# OpenReader_Schematic.net
KiCad netlist of a schematic drawn in EAGLE
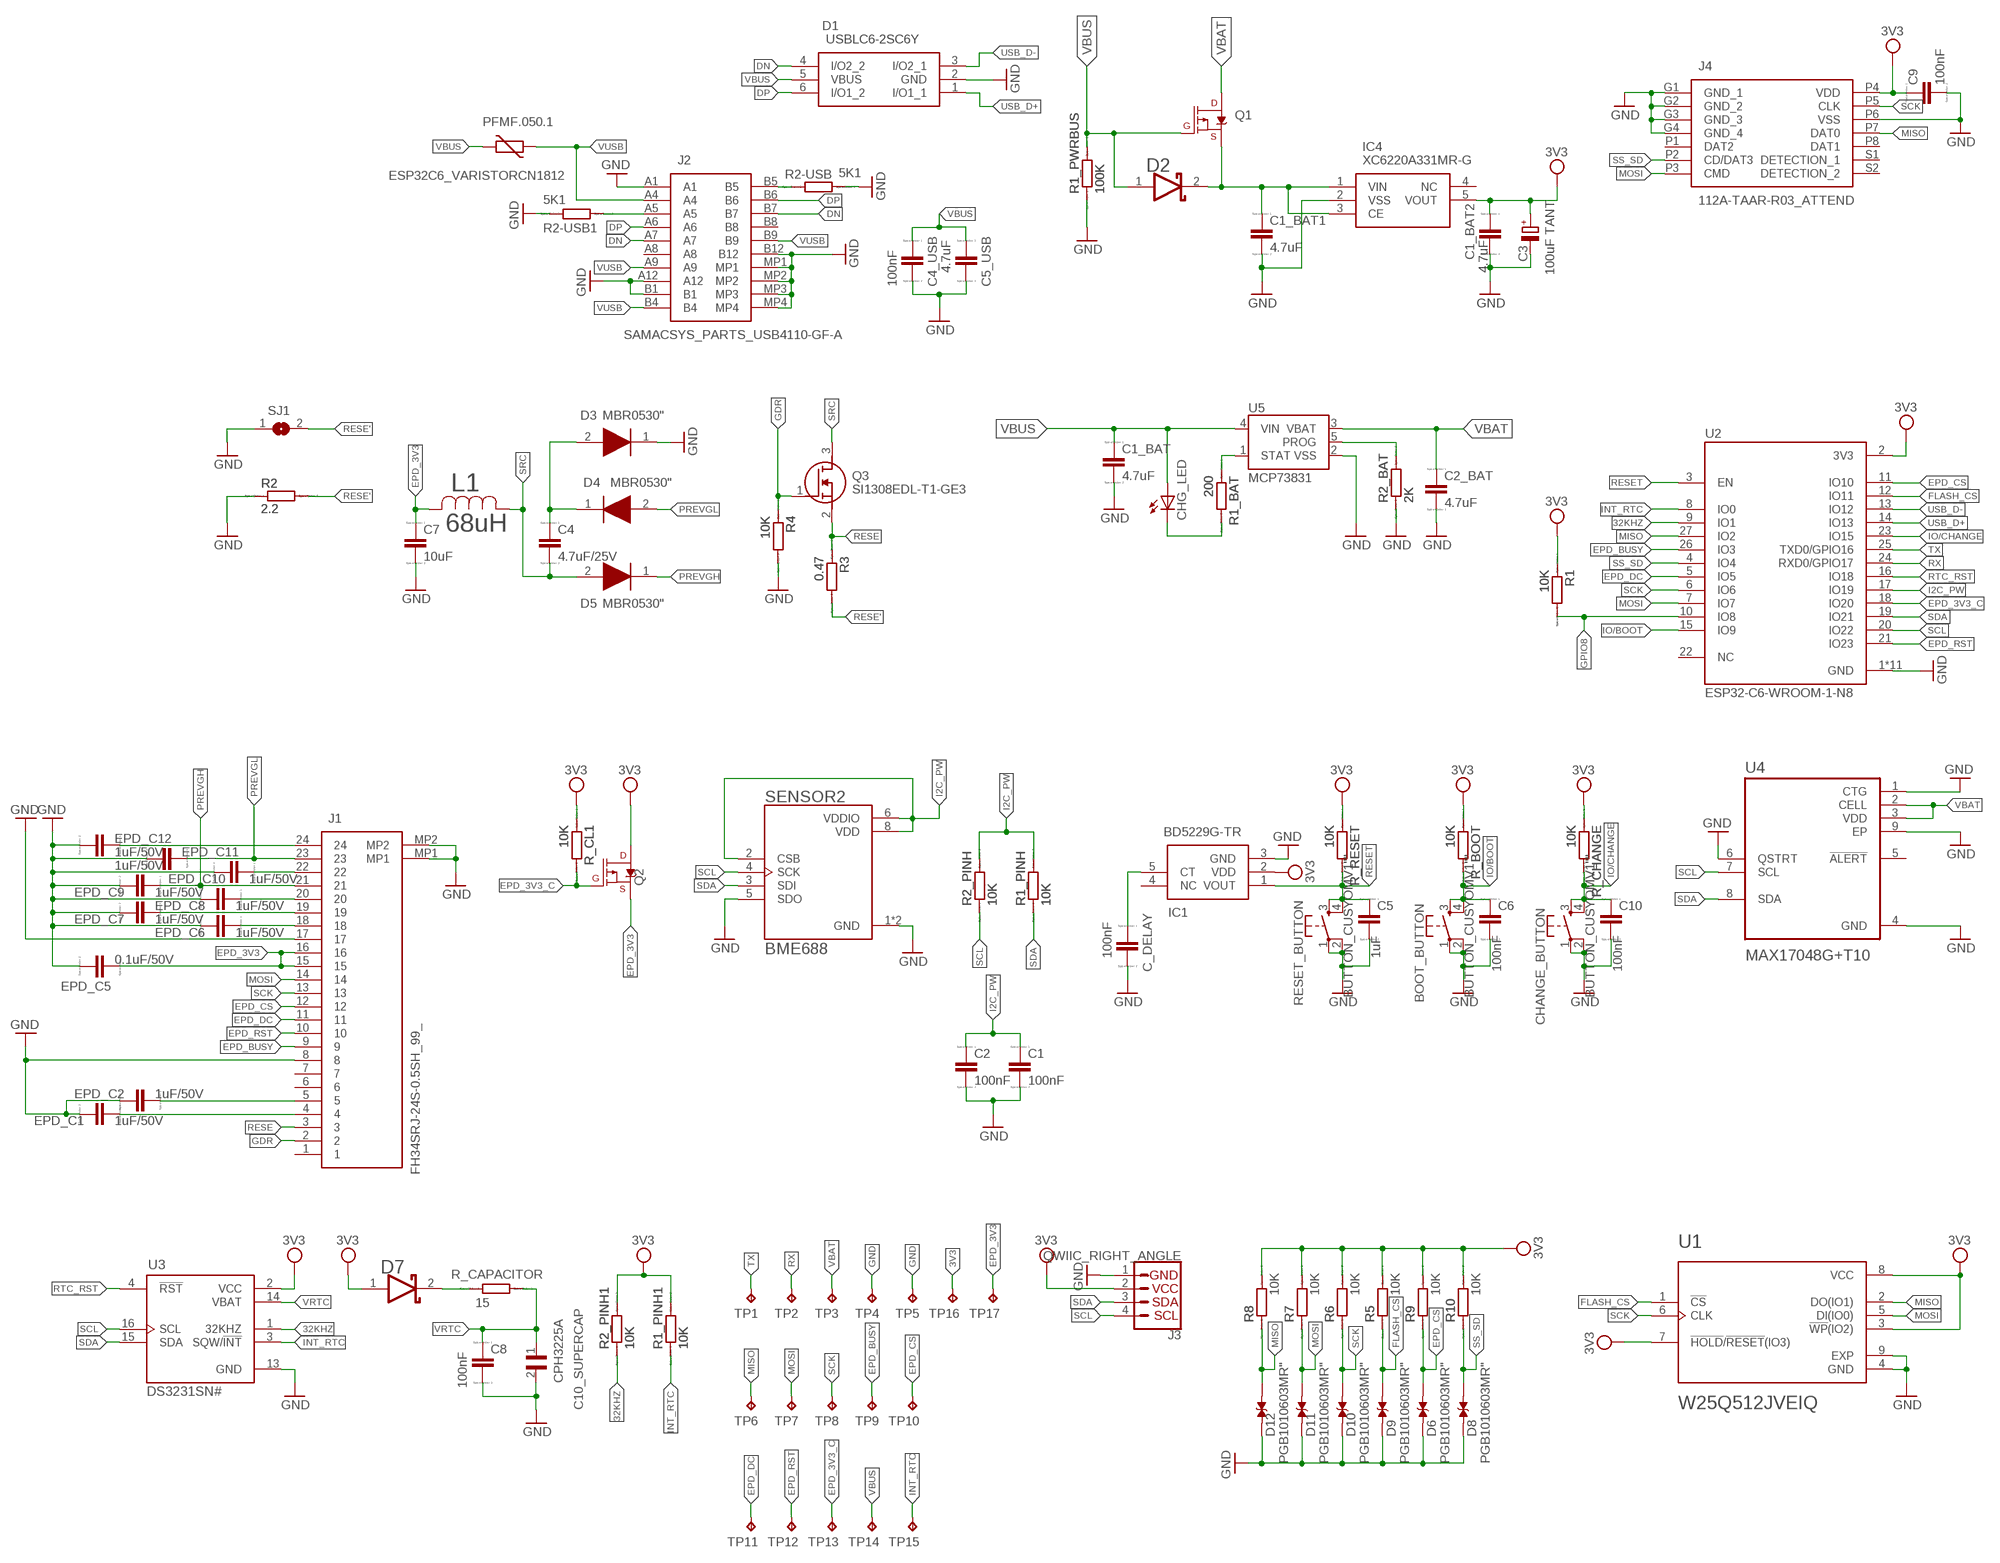
[diagram p0: schematic, sheet 1]

(export (version "E")
  (design (tool "Eeschema 10.0.6"))
  (components
    (comp (ref "BOOT_BUTTON")
      (value "BUTTON_CUSYOMV1\"\"")
      (footprint "eagle-import:MYBUTTON")
      (libsource (lib "eagle-import") (part "BUTTON_CUSYOMV1{dblquote}"))
    )
    (comp (ref "C1")
      (value "100nF")
      (footprint "eagle-import:EAGLE-LTSPICE_C0402")
      (libsource (lib "eagle-import") (part "EAGLE-LTSPICE_CC0402"))
    )
    (comp (ref "C1_BAT")
      (value "4.7uF")
      (footprint "eagle-import:EAGLE-LTSPICE_C0402")
      (libsource (lib "eagle-import") (part "EAGLE-LTSPICE_CC0402"))
    )
    (comp (ref "C1_BAT1")
      (value "4.7uF")
      (footprint "eagle-import:EAGLE-LTSPICE_C0402")
      (libsource (lib "eagle-import") (part "EAGLE-LTSPICE_CC0402"))
    )
    (comp (ref "C1_BAT2")
      (value "4.7uF")
      (footprint "eagle-import:EAGLE-LTSPICE_C0402")
      (libsource (lib "eagle-import") (part "EAGLE-LTSPICE_CC0402"))
    )
    (comp (ref "C2")
      (value "100nF")
      (footprint "eagle-import:EAGLE-LTSPICE_C0402")
      (libsource (lib "eagle-import") (part "EAGLE-LTSPICE_CC0402"))
    )
    (comp (ref "C2_BAT")
      (value "4.7uF")
      (footprint "eagle-import:EAGLE-LTSPICE_C0402")
      (libsource (lib "eagle-import") (part "EAGLE-LTSPICE_CC0402"))
    )
    (comp (ref "C3")
      (value "100uF TANT")
      (footprint "eagle-import:RCL_CT3528")
      (libsource (lib "eagle-import") (part "RCL_CPOL-EUCT3528"))
    )
    (comp (ref "C4")
      (value "4.7uF/25V")
      (footprint "eagle-import:EAGLE-LTSPICE_C0402")
      (libsource (lib "eagle-import") (part "EAGLE-LTSPICE_CC0402"))
    )
    (comp (ref "C4_USB")
      (value "100nF")
      (footprint "eagle-import:EAGLE-LTSPICE_C0402")
      (libsource (lib "eagle-import") (part "EAGLE-LTSPICE_CC0402"))
    )
    (comp (ref "C5")
      (value "1uF")
      (footprint "eagle-import:EAGLE-LTSPICE_C0402")
      (libsource (lib "eagle-import") (part "EAGLE-LTSPICE_CC0402"))
    )
    (comp (ref "C5_USB")
      (value "4.7uF")
      (footprint "eagle-import:EAGLE-LTSPICE_C0402")
      (libsource (lib "eagle-import") (part "EAGLE-LTSPICE_CC0402"))
    )
    (comp (ref "C6")
      (value "100nF")
      (footprint "eagle-import:EAGLE-LTSPICE_C0402")
      (libsource (lib "eagle-import") (part "EAGLE-LTSPICE_CC0402"))
    )
    (comp (ref "C7")
      (value "10uF")
      (footprint "eagle-import:EAGLE-LTSPICE_C0402")
      (libsource (lib "eagle-import") (part "EAGLE-LTSPICE_CC0402"))
    )
    (comp (ref "C8")
      (value "100nF")
      (footprint "eagle-import:EAGLE-LTSPICE_C0402")
      (libsource (lib "eagle-import") (part "EAGLE-LTSPICE_CC0402"))
    )
    (comp (ref "C9")
      (value "100nF")
      (footprint "eagle-import:EAGLE-LTSPICE_C0402")
      (libsource (lib "eagle-import") (part "EAGLE-LTSPICE_CC0402"))
    )
    (comp (ref "C10")
      (value "100nF")
      (footprint "eagle-import:EAGLE-LTSPICE_C0402")
      (libsource (lib "eagle-import") (part "EAGLE-LTSPICE_CC0402"))
    )
    (comp (ref "C10_SUPERCAP")
      (value "CPH3225A")
      (footprint "eagle-import:CAPCP3225X100N")
      (fields (field (name "MF") "Seiko Instruments"))
      (libsource (lib "eagle-import") (part "CPH3225A"))
    )
    (comp (ref "CHANGE_BUTTON")
      (value "BUTTON_CUSYOMV1\"\"")
      (footprint "eagle-import:MYBUTTON")
      (libsource (lib "eagle-import") (part "BUTTON_CUSYOMV1{dblquote}"))
    )
    (comp (ref "CHG_LED")
      (value "ADAFRUIT_LEDCHIP-LED0603")
      (footprint "eagle-import:ADAFRUIT_CHIP-LED0603")
      (libsource (lib "eagle-import") (part "ADAFRUIT_LEDCHIP-LED0603"))
    )
    (comp (ref "C_DELAY")
      (value "100nF")
      (footprint "eagle-import:EAGLE-LTSPICE_C0402")
      (libsource (lib "eagle-import") (part "EAGLE-LTSPICE_CC0402"))
    )
    (comp (ref "D1")
      (value "USBLC6-2SC6Y")
      (footprint "eagle-import:SOT95P280X145-6N")
      (fields (field (name "MF") "STMicroelectronics"))
      (libsource (lib "eagle-import") (part "USBLC6-2SC6Y"))
    )
    (comp (ref "D2")
      (value "ESP32_WROVER_AVX---SD0805S020S1R0_AVX_SD0805S020S1R0_0_0AVX_SD0805S020S1R0_0_0")
      (footprint "eagle-import:ESP32_WROVER_AVX---SD0805S020S1R0_AVX_SD0805S020S1R0_0")
      (libsource (lib "eagle-import") (part "ESP32_WROVER_AVX---SD0805S020S1R0_AVX_SD0805S020S1R0_0_0AVX_SD0805S020S1R0_0_0"))
    )
    (comp (ref "D3")
      (value "MBR0530\"")
      (footprint "eagle-import:SOD3716X135N")
      (libsource (lib "eagle-import") (part "MBR0530{dblquote}"))
    )
    (comp (ref "D4")
      (value "MBR0530\"")
      (footprint "eagle-import:SOD3716X135N")
      (libsource (lib "eagle-import") (part "MBR0530{dblquote}"))
    )
    (comp (ref "D5")
      (value "MBR0530\"")
      (footprint "eagle-import:SOD3716X135N")
      (libsource (lib "eagle-import") (part "MBR0530{dblquote}"))
    )
    (comp (ref "D6")
      (value "PGB1010603MR\"")
      (footprint "eagle-import:DIOC1608X36N")
      (libsource (lib "eagle-import") (part "PGB1010603MR{dblquote}"))
    )
    (comp (ref "D7")
      (value "ESP32_WROVER_AVX---SD0805S020S1R0_AVX_SD0805S020S1R0_0_0AVX_SD0805S020S1R0_0_0")
      (footprint "eagle-import:ESP32_WROVER_AVX---SD0805S020S1R0_AVX_SD0805S020S1R0_0")
      (libsource (lib "eagle-import") (part "ESP32_WROVER_AVX---SD0805S020S1R0_AVX_SD0805S020S1R0_0_0AVX_SD0805S020S1R0_0_0"))
    )
    (comp (ref "D8")
      (value "PGB1010603MR\"")
      (footprint "eagle-import:DIOC1608X36N")
      (libsource (lib "eagle-import") (part "PGB1010603MR{dblquote}"))
    )
    (comp (ref "D9")
      (value "PGB1010603MR\"")
      (footprint "eagle-import:DIOC1608X36N")
      (libsource (lib "eagle-import") (part "PGB1010603MR{dblquote}"))
    )
    (comp (ref "D10")
      (value "PGB1010603MR\"")
      (footprint "eagle-import:DIOC1608X36N")
      (libsource (lib "eagle-import") (part "PGB1010603MR{dblquote}"))
    )
    (comp (ref "D11")
      (value "PGB1010603MR\"")
      (footprint "eagle-import:DIOC1608X36N")
      (libsource (lib "eagle-import") (part "PGB1010603MR{dblquote}"))
    )
    (comp (ref "D12")
      (value "PGB1010603MR\"")
      (footprint "eagle-import:DIOC1608X36N")
      (libsource (lib "eagle-import") (part "PGB1010603MR{dblquote}"))
    )
    (comp (ref "EPD_C1")
      (value "1uF/50V")
      (footprint "eagle-import:EAGLE-LTSPICE_C0402")
      (libsource (lib "eagle-import") (part "EAGLE-LTSPICE_CC0402"))
    )
    (comp (ref "EPD_C2")
      (value "1uF/50V")
      (footprint "eagle-import:EAGLE-LTSPICE_C0402")
      (libsource (lib "eagle-import") (part "EAGLE-LTSPICE_CC0402"))
    )
    (comp (ref "EPD_C5")
      (value "0.1uF/50V")
      (footprint "eagle-import:EAGLE-LTSPICE_C0402")
      (libsource (lib "eagle-import") (part "EAGLE-LTSPICE_CC0402"))
    )
    (comp (ref "EPD_C6")
      (value "1uF/50V")
      (footprint "eagle-import:EAGLE-LTSPICE_C0402")
      (libsource (lib "eagle-import") (part "EAGLE-LTSPICE_CC0402"))
    )
    (comp (ref "EPD_C7")
      (value "1uF/50V")
      (footprint "eagle-import:EAGLE-LTSPICE_C0402")
      (libsource (lib "eagle-import") (part "EAGLE-LTSPICE_CC0402"))
    )
    (comp (ref "EPD_C8")
      (value "1uF/50V")
      (footprint "eagle-import:EAGLE-LTSPICE_C0402")
      (libsource (lib "eagle-import") (part "EAGLE-LTSPICE_CC0402"))
    )
    (comp (ref "EPD_C9")
      (value "1uF/50V")
      (footprint "eagle-import:EAGLE-LTSPICE_C0402")
      (libsource (lib "eagle-import") (part "EAGLE-LTSPICE_CC0402"))
    )
    (comp (ref "EPD_C10")
      (value "1uF/50V")
      (footprint "eagle-import:EAGLE-LTSPICE_C0402")
      (libsource (lib "eagle-import") (part "EAGLE-LTSPICE_CC0402"))
    )
    (comp (ref "EPD_C11")
      (value "1uF/50V")
      (footprint "eagle-import:EAGLE-LTSPICE_C0402")
      (libsource (lib "eagle-import") (part "EAGLE-LTSPICE_CC0402"))
    )
    (comp (ref "EPD_C12")
      (value "1uF/50V")
      (footprint "eagle-import:EAGLE-LTSPICE_C0402")
      (libsource (lib "eagle-import") (part "EAGLE-LTSPICE_CC0402"))
    )
    (comp (ref "IC1")
      (value "BD5229G-TR")
      (footprint "eagle-import:SOT95P280X125-5N")
      (fields (field (name "MOUSER_PART_NUMBER") "755-BD5229G-TR"))
      (libsource (lib "eagle-import") (part "BD5229G-TR"))
    )
    (comp (ref "IC4")
      (value "XC6220A331MR-G")
      (footprint "eagle-import:SOT95P280X120-5N")
      (fields (field (name "MOUSER_PART_NUMBER") "865-XC6220A331MR-G"))
      (libsource (lib "eagle-import") (part "XC6220A331MR-G"))
    )
    (comp (ref "J1")
      (value "FH34SRJ-24S-0.5SH_99_")
      (footprint "eagle-import:FH34SRJ24S05SH99")
      (fields
        (field (name "MANUFACTURER_PART_NUMBER") "FH34SRJ-24S-0.5SH(99)")
        (field (name "MOUSER_PART_NUMBER") "798-FH34SRJ24S05SH99")
      )
      (libsource (lib "eagle-import") (part "FH34SRJ-24S-0.5SH_99_"))
    )
    (comp (ref "J2")
      (value "SAMACSYS_PARTS_USB4110-GF-A")
      (footprint "eagle-import:SAMACSYS_PARTS_USB4110GFA")
      (fields
        (field (name "MANUFACTURER_PART_NUMBER") "USB4110-GF-A")
        (field (name "MOUSER_PART_NUMBER") "640-USB4110-GF-A")
      )
      (libsource (lib "eagle-import") (part "SAMACSYS_PARTS_USB4110-GF-A"))
    )
    (comp (ref "J3")
      (value "QWIIC_RIGHT_ANGLE")
      (footprint "eagle-import:JST04_1MM_RA")
      (libsource (lib "eagle-import") (part "QWIIC_CONNECTORJS-1MM"))
    )
    (comp (ref "J4")
      (value "112A-TAAR-R03_ATTEND")
      (footprint "eagle-import:112ATAARR03ATTEND")
      (fields (field (name "MANUFACTURER_PART_NUMBER") "112A-TAAR-R03 ATTEND"))
      (libsource (lib "eagle-import") (part "112A-TAAR-R03_ATTEND"))
    )
    (comp (ref "L1")
      (value "68uH")
      (footprint "eagle-import:IND_4828-WE-TPC_WRE")
      (fields
        (field (name "MANUFACTURER_PART_NUMBER") "744043680")
        (field (name "COPYRIGHT") "Copyright (C) 2024 Ultra Librarian. All rights reserved.")
      )
      (libsource (lib "eagle-import") (part "744043680IND_4828-WE-TPC_WRE"))
    )
    (comp (ref "PFMF.050.1")
      (value "ESP32C6_VARISTORCN1812")
      (footprint "eagle-import:ESP32C6_VARISTOR_CT_CN1812")
      (libsource (lib "eagle-import") (part "ESP32C6_VARISTORCN1812"))
    )
    (comp (ref "Q1")
      (value "20V/4.2A/52mΩ/1.4W")
      (footprint "eagle-import:ESP32_WROVER_SPARKFUN-DISCRETESEMI_SOT23-3")
      (libsource (lib "eagle-import") (part "ESP32_WROVER_SPARKFUN-DISCRETESEMI_MOSFET_PCH-DMG2305UX-7"))
    )
    (comp (ref "Q2")
      (value "20V/4.2A/52mΩ/1.4W")
      (footprint "eagle-import:ESP32_WROVER_SPARKFUN-DISCRETESEMI_SOT23-3")
      (libsource (lib "eagle-import") (part "ESP32_WROVER_SPARKFUN-DISCRETESEMI_MOSFET_PCH-DMG2305UX-7"))
    )
    (comp (ref "Q3")
      (value "SI1308EDL-T1-GE3")
      (footprint "eagle-import:SOT65P210X110-3N")
      (fields (field (name "MF") "Vishay Siliconix"))
      (libsource (lib "eagle-import") (part "SI1308EDL-T1-GE3"))
    )
    (comp (ref "R1")
      (value "10K")
      (footprint "eagle-import:ESP32_WROVER_EAGLE-LTSPICE_R0402")
      (libsource (lib "eagle-import") (part "ESP32_WROVER_EAGLE-LTSPICE_RR0402"))
    )
    (comp (ref "R1_BAT")
      (value "200")
      (footprint "eagle-import:ESP32_WROVER_EAGLE-LTSPICE_R0402")
      (libsource (lib "eagle-import") (part "ESP32_WROVER_EAGLE-LTSPICE_RR0402"))
    )
    (comp (ref "R1_PINH")
      (value "10K")
      (footprint "eagle-import:ESP32_WROVER_EAGLE-LTSPICE_R0402")
      (libsource (lib "eagle-import") (part "ESP32_WROVER_EAGLE-LTSPICE_RR0402"))
    )
    (comp (ref "R1_PINH1")
      (value "10K")
      (footprint "eagle-import:ESP32_WROVER_EAGLE-LTSPICE_R0402")
      (libsource (lib "eagle-import") (part "ESP32_WROVER_EAGLE-LTSPICE_RR0402"))
    )
    (comp (ref "R1_PWRBUS")
      (value "100K")
      (footprint "eagle-import:ESP32_WROVER_EAGLE-LTSPICE_R0402")
      (libsource (lib "eagle-import") (part "ESP32_WROVER_EAGLE-LTSPICE_RR0402"))
    )
    (comp (ref "R2")
      (value "2.2")
      (footprint "eagle-import:ESP32_WROVER_EAGLE-LTSPICE_R0402")
      (libsource (lib "eagle-import") (part "ESP32_WROVER_EAGLE-LTSPICE_RR0402"))
    )
    (comp (ref "R2-USB")
      (value "5K1")
      (footprint "eagle-import:ESP32_WROVER_EAGLE-LTSPICE_R0402")
      (libsource (lib "eagle-import") (part "ESP32_WROVER_EAGLE-LTSPICE_RR0402"))
    )
    (comp (ref "R2-USB1")
      (value "5K1")
      (footprint "eagle-import:ESP32_WROVER_EAGLE-LTSPICE_R0402")
      (libsource (lib "eagle-import") (part "ESP32_WROVER_EAGLE-LTSPICE_RR0402"))
    )
    (comp (ref "R2_BAT")
      (value "2K")
      (footprint "eagle-import:ESP32_WROVER_EAGLE-LTSPICE_R0402")
      (libsource (lib "eagle-import") (part "ESP32_WROVER_EAGLE-LTSPICE_RR0402"))
    )
    (comp (ref "R2_PINH")
      (value "10K")
      (footprint "eagle-import:ESP32_WROVER_EAGLE-LTSPICE_R0402")
      (libsource (lib "eagle-import") (part "ESP32_WROVER_EAGLE-LTSPICE_RR0402"))
    )
    (comp (ref "R2_PINH1")
      (value "10K")
      (footprint "eagle-import:ESP32_WROVER_EAGLE-LTSPICE_R0402")
      (libsource (lib "eagle-import") (part "ESP32_WROVER_EAGLE-LTSPICE_RR0402"))
    )
    (comp (ref "R3")
      (value "0.47")
      (footprint "eagle-import:ESP32_WROVER_EAGLE-LTSPICE_R0402")
      (libsource (lib "eagle-import") (part "ESP32_WROVER_EAGLE-LTSPICE_RR0402"))
    )
    (comp (ref "R4")
      (value "10K")
      (footprint "eagle-import:ESP32_WROVER_EAGLE-LTSPICE_R0402")
      (libsource (lib "eagle-import") (part "ESP32_WROVER_EAGLE-LTSPICE_RR0402"))
    )
    (comp (ref "R5")
      (value "10K")
      (footprint "eagle-import:ESP32_WROVER_EAGLE-LTSPICE_R0402")
      (libsource (lib "eagle-import") (part "ESP32_WROVER_EAGLE-LTSPICE_RR0402"))
    )
    (comp (ref "R6")
      (value "10K")
      (footprint "eagle-import:ESP32_WROVER_EAGLE-LTSPICE_R0402")
      (libsource (lib "eagle-import") (part "ESP32_WROVER_EAGLE-LTSPICE_RR0402"))
    )
    (comp (ref "R7")
      (value "10K")
      (footprint "eagle-import:ESP32_WROVER_EAGLE-LTSPICE_R0402")
      (libsource (lib "eagle-import") (part "ESP32_WROVER_EAGLE-LTSPICE_RR0402"))
    )
    (comp (ref "R8")
      (value "10K")
      (footprint "eagle-import:ESP32_WROVER_EAGLE-LTSPICE_R0402")
      (libsource (lib "eagle-import") (part "ESP32_WROVER_EAGLE-LTSPICE_RR0402"))
    )
    (comp (ref "R9")
      (value "10K")
      (footprint "eagle-import:ESP32_WROVER_EAGLE-LTSPICE_R0402")
      (libsource (lib "eagle-import") (part "ESP32_WROVER_EAGLE-LTSPICE_RR0402"))
    )
    (comp (ref "R10")
      (value "10K")
      (footprint "eagle-import:ESP32_WROVER_EAGLE-LTSPICE_R0402")
      (libsource (lib "eagle-import") (part "ESP32_WROVER_EAGLE-LTSPICE_RR0402"))
    )
    (comp (ref "RESET_BUTTON")
      (value "BUTTON_CUSYOMV1\"\"")
      (footprint "eagle-import:MYBUTTON")
      (libsource (lib "eagle-import") (part "BUTTON_CUSYOMV1{dblquote}"))
    )
    (comp (ref "R_BOOT")
      (value "10K")
      (footprint "eagle-import:ESP32_WROVER_EAGLE-LTSPICE_R0402")
      (libsource (lib "eagle-import") (part "ESP32_WROVER_EAGLE-LTSPICE_RR0402"))
    )
    (comp (ref "R_CAPACITOR")
      (value "15")
      (footprint "eagle-import:ESP32_WROVER_EAGLE-LTSPICE_R0402")
      (libsource (lib "eagle-import") (part "ESP32_WROVER_EAGLE-LTSPICE_RR0402"))
    )
    (comp (ref "R_CHANGE")
      (value "10K")
      (footprint "eagle-import:ESP32_WROVER_EAGLE-LTSPICE_R0402")
      (libsource (lib "eagle-import") (part "ESP32_WROVER_EAGLE-LTSPICE_RR0402"))
    )
    (comp (ref "R_CL1")
      (value "10K")
      (footprint "eagle-import:ESP32_WROVER_EAGLE-LTSPICE_R0402")
      (libsource (lib "eagle-import") (part "ESP32_WROVER_EAGLE-LTSPICE_RR0402"))
    )
    (comp (ref "R_RESET")
      (value "10K")
      (footprint "eagle-import:ESP32_WROVER_EAGLE-LTSPICE_R0402")
      (libsource (lib "eagle-import") (part "ESP32_WROVER_EAGLE-LTSPICE_RR0402"))
    )
    (comp (ref "SENSOR2")
      (value "BME688")
      (footprint "eagle-import:ESP32_WROVER_BME680_PSON80P300X300X100-8N")
      (fields (field (name "MF") "Bosch Sensortec") (field (name "MP") "BME680"))
      (libsource (lib "eagle-import") (part "ESP32_WROVER_BME680_BME680"))
    )
    (comp (ref "SJ1") (value "SJ") (footprint "eagle-import:SJ") (libsource (lib "eagle-import") (part "SJ")))
    (comp (ref "TP1")
      (value "TPTP20R")
      (footprint "eagle-import:TP20R")
      (libsource (lib "eagle-import") (part "TPTP20R"))
    )
    (comp (ref "TP2")
      (value "TPTP20R")
      (footprint "eagle-import:TP20R")
      (libsource (lib "eagle-import") (part "TPTP20R"))
    )
    (comp (ref "TP3")
      (value "TPTP20R")
      (footprint "eagle-import:TP20R")
      (libsource (lib "eagle-import") (part "TPTP20R"))
    )
    (comp (ref "TP4")
      (value "TPTP20R")
      (footprint "eagle-import:TP20R")
      (libsource (lib "eagle-import") (part "TPTP20R"))
    )
    (comp (ref "TP5")
      (value "TPTP20R")
      (footprint "eagle-import:TP20R")
      (libsource (lib "eagle-import") (part "TPTP20R"))
    )
    (comp (ref "TP6")
      (value "TPTP20R")
      (footprint "eagle-import:TP20R")
      (libsource (lib "eagle-import") (part "TPTP20R"))
    )
    (comp (ref "TP7")
      (value "TPTP20R")
      (footprint "eagle-import:TP20R")
      (libsource (lib "eagle-import") (part "TPTP20R"))
    )
    (comp (ref "TP8")
      (value "TPTP20R")
      (footprint "eagle-import:TP20R")
      (libsource (lib "eagle-import") (part "TPTP20R"))
    )
    (comp (ref "TP9")
      (value "TPTP20R")
      (footprint "eagle-import:TP20R")
      (libsource (lib "eagle-import") (part "TPTP20R"))
    )
    (comp (ref "TP10")
      (value "TPTP20R")
      (footprint "eagle-import:TP20R")
      (libsource (lib "eagle-import") (part "TPTP20R"))
    )
    (comp (ref "TP11")
      (value "TPTP20R")
      (footprint "eagle-import:TP20R")
      (libsource (lib "eagle-import") (part "TPTP20R"))
    )
    (comp (ref "TP12")
      (value "TPTP20R")
      (footprint "eagle-import:TP20R")
      (libsource (lib "eagle-import") (part "TPTP20R"))
    )
    (comp (ref "TP13")
      (value "TPTP20R")
      (footprint "eagle-import:TP20R")
      (libsource (lib "eagle-import") (part "TPTP20R"))
    )
    (comp (ref "TP14")
      (value "TPTP20R")
      (footprint "eagle-import:TP20R")
      (libsource (lib "eagle-import") (part "TPTP20R"))
    )
    (comp (ref "TP15")
      (value "TPTP20R")
      (footprint "eagle-import:TP20R")
      (libsource (lib "eagle-import") (part "TPTP20R"))
    )
    (comp (ref "TP16")
      (value "TPTP20R")
      (footprint "eagle-import:TP20R")
      (libsource (lib "eagle-import") (part "TPTP20R"))
    )
    (comp (ref "TP17")
      (value "TPTP20R")
      (footprint "eagle-import:TP20R")
      (libsource (lib "eagle-import") (part "TPTP20R"))
    )
    (comp (ref "U1")
      (value "W25Q512JVEIQ")
      (footprint "eagle-import:SON127P600X800X80-9N")
      (fields (field (name "MF") "Winbond Electronics"))
      (libsource (lib "eagle-import") (part "W25Q512JVEIQ"))
    )
    (comp (ref "U2")
      (value "ESP32-C6-WROOM-1-N8")
      (footprint "eagle-import:XCVR_ESP32-C6-WROOM-1-N8")
      (fields (field (name "MF") "Espressif Systems"))
      (libsource (lib "eagle-import") (part "ESP32-C6-WROOM-1-N8"))
    )
    (comp (ref "U3")
      (value "DS3231SN#")
      (footprint "eagle-import:SOIC127P1032X265-16N")
      (fields (field (name "MF") "Analog Devices"))
      (libsource (lib "eagle-import") (part "DS3231SN#"))
    )
    (comp (ref "U4")
      (value "MAX17048G+T10")
      (footprint "eagle-import:SON50P200X200X80-9N")
      (fields (field (name "MF") "Analog Devices"))
      (libsource (lib "eagle-import") (part "MAX17048G+T10"))
    )
    (comp (ref "U5")
      (value "MCP73831")
      (footprint "eagle-import:SOT23-5")
      (libsource (lib "eagle-import") (part "MCP73831"))
    )
  )
  (nets
    (net (code "1") (name "3V3") (class "Default")
      (node (ref "C1_BAT2") (pin "1") (pinfunction "1_1") (pintype "passive"))
      (node (ref "C3") (pin "+") (pinfunction "+_+") (pintype "passive"))
      (node (ref "C9") (pin "1") (pinfunction "1_1") (pintype "passive"))
      (node (ref "D7") (pin "1") (pinfunction "ANODE_1") (pintype "bidirectional"))
      (node (ref "IC1") (pin "2") (pinfunction "VDD_2") (pintype "bidirectional"))
      (node (ref "IC4") (pin "5") (pinfunction "VOUT_5") (pintype "bidirectional"))
      (node (ref "J3") (pin "2") (pinfunction "2_2") (pintype "power_in"))
      (node (ref "J4") (pin "P4") (pinfunction "VDD_P4") (pintype "bidirectional"))
      (node (ref "Q2") (pin "3") (pinfunction "D_3") (pintype "bidirectional"))
      (node (ref "R1") (pin "1") (pinfunction "1_1") (pintype "passive"))
      (node (ref "R10") (pin "2") (pinfunction "2_2") (pintype "passive"))
      (node (ref "R1_PINH1") (pin "2") (pinfunction "2_2") (pintype "passive"))
      (node (ref "R2_PINH1") (pin "2") (pinfunction "2_2") (pintype "passive"))
      (node (ref "R5") (pin "2") (pinfunction "2_2") (pintype "passive"))
      (node (ref "R6") (pin "2") (pinfunction "2_2") (pintype "passive"))
      (node (ref "R7") (pin "2") (pinfunction "2_2") (pintype "passive"))
      (node (ref "R8") (pin "2") (pinfunction "2_2") (pintype "passive"))
      (node (ref "R9") (pin "2") (pinfunction "2_2") (pintype "passive"))
      (node (ref "R_BOOT") (pin "1") (pinfunction "1_1") (pintype "passive"))
      (node (ref "R_CHANGE") (pin "1") (pinfunction "1_1") (pintype "passive"))
      (node (ref "R_CL1") (pin "1") (pinfunction "1_1") (pintype "passive"))
      (node (ref "R_RESET") (pin "1") (pinfunction "1_1") (pintype "passive"))
      (node (ref "TP16") (pin "TP") (pinfunction "TP_TP") (pintype "input"))
      (node (ref "U1") (pin "3") (pinfunction "~{WP}(IO2)_3") (pintype "bidirectional"))
      (node (ref "U1") (pin "7") (pinfunction "~{HOLD}/~{RESET}(IO3)_7") (pintype "bidirectional"))
      (node (ref "U1") (pin "8") (pinfunction "VCC_8") (pintype "power_in"))
      (node (ref "U2") (pin "2") (pinfunction "3V3_2") (pintype "power_in"))
      (node (ref "U3") (pin "2") (pinfunction "VCC_2") (pintype "power_in"))
    )
    (net (code "2") (name "32KHZ") (class "Default")
      (node (ref "R2_PINH1") (pin "1") (pinfunction "1_1") (pintype "passive"))
      (node (ref "U2") (pin "9") (pinfunction "IO1_9") (pintype "bidirectional"))
      (node (ref "U3") (pin "1") (pinfunction "32KHZ_1") (pintype "output"))
    )
    (net (code "3") (name "DN") (class "Default")
      (node (ref "D1") (pin "4") (pinfunction "I/O2_2_4") (pintype "bidirectional"))
      (node (ref "J2") (pin "A7") (pinfunction "A7_A7") (pintype "bidirectional"))
      (node (ref "J2") (pin "B7") (pinfunction "B7_B7") (pintype "bidirectional"))
    )
    (net (code "4") (name "DP") (class "Default")
      (node (ref "D1") (pin "6") (pinfunction "I/O1_2_6") (pintype "bidirectional"))
      (node (ref "J2") (pin "A6") (pinfunction "A6_A6") (pintype "bidirectional"))
      (node (ref "J2") (pin "B6") (pinfunction "B6_B6") (pintype "bidirectional"))
    )
    (net (code "5") (name "EPD_3V3") (class "Default")
      (node (ref "C7") (pin "1") (pinfunction "1_1") (pintype "passive"))
      (node (ref "EPD_C5") (pin "1") (pinfunction "1_1") (pintype "passive"))
      (node (ref "J1") (pin "15") (pinfunction "15_15") (pintype "bidirectional"))
      (node (ref "J1") (pin "16") (pinfunction "16_16") (pintype "bidirectional"))
      (node (ref "L1") (pin "2") (pinfunction "2_2") (pintype "passive"))
      (node (ref "Q2") (pin "2") (pinfunction "S_2") (pintype "bidirectional"))
      (node (ref "TP17") (pin "TP") (pinfunction "TP_TP") (pintype "input"))
    )
    (net (code "6") (name "EPD_3V3_C") (class "Default")
      (node (ref "Q2") (pin "1") (pinfunction "G_1") (pintype "bidirectional"))
      (node (ref "R_CL1") (pin "2") (pinfunction "2_2") (pintype "passive"))
      (node (ref "TP13") (pin "TP") (pinfunction "TP_TP") (pintype "input"))
      (node (ref "U2") (pin "18") (pinfunction "IO20_18") (pintype "bidirectional"))
    )
    (net (code "7") (name "EPD_BUSY") (class "Default")
      (node (ref "J1") (pin "9") (pinfunction "9_9") (pintype "bidirectional"))
      (node (ref "TP9") (pin "TP") (pinfunction "TP_TP") (pintype "input"))
      (node (ref "U2") (pin "26") (pinfunction "IO3_26") (pintype "bidirectional"))
    )
    (net (code "8") (name "EPD_CS") (class "Default")
      (node (ref "D6") (pin "2") (pinfunction "2_2") (pintype "passive"))
      (node (ref "J1") (pin "12") (pinfunction "12_12") (pintype "bidirectional"))
      (node (ref "R9") (pin "1") (pinfunction "1_1") (pintype "passive"))
      (node (ref "TP10") (pin "TP") (pinfunction "TP_TP") (pintype "input"))
      (node (ref "U2") (pin "11") (pinfunction "IO10_11") (pintype "bidirectional"))
    )
    (net (code "9") (name "EPD_DC") (class "Default")
      (node (ref "J1") (pin "11") (pinfunction "11_11") (pintype "bidirectional"))
      (node (ref "TP11") (pin "TP") (pinfunction "TP_TP") (pintype "input"))
      (node (ref "U2") (pin "5") (pinfunction "IO5_5") (pintype "bidirectional"))
    )
    (net (code "10") (name "EPD_RST") (class "Default")
      (node (ref "J1") (pin "10") (pinfunction "10_10") (pintype "bidirectional"))
      (node (ref "TP12") (pin "TP") (pinfunction "TP_TP") (pintype "input"))
      (node (ref "U2") (pin "21") (pinfunction "IO23_21") (pintype "bidirectional"))
    )
    (net (code "11") (name "FLASH_CS") (class "Default")
      (node (ref "D9") (pin "2") (pinfunction "2_2") (pintype "passive"))
      (node (ref "R5") (pin "1") (pinfunction "1_1") (pintype "passive"))
      (node (ref "U1") (pin "1") (pinfunction "~{CS}_1") (pintype "input"))
      (node (ref "U2") (pin "12") (pinfunction "IO11_12") (pintype "bidirectional"))
    )
    (net (code "12") (name "GDR") (class "Default")
      (node (ref "J1") (pin "2") (pinfunction "2_2") (pintype "bidirectional"))
      (node (ref "Q3") (pin "1") (pinfunction "G_1") (pintype "bidirectional"))
      (node (ref "R4") (pin "1") (pinfunction "1_1") (pintype "passive"))
    )
    (net (code "13") (name "GND") (class "Default")
      (node (ref "BOOT_BUTTON") (pin "1") (pinfunction "1_1") (pintype "passive"))
      (node (ref "BOOT_BUTTON") (pin "2") (pinfunction "2_2") (pintype "passive"))
      (node (ref "C1") (pin "2") (pinfunction "2_2") (pintype "passive"))
      (node (ref "C10") (pin "2") (pinfunction "2_2") (pintype "passive"))
      (node (ref "C10_SUPERCAP") (pin "2") (pinfunction "2_2") (pintype "passive"))
      (node (ref "C1_BAT") (pin "2") (pinfunction "2_2") (pintype "passive"))
      (node (ref "C1_BAT1") (pin "2") (pinfunction "2_2") (pintype "passive"))
      (node (ref "C1_BAT2") (pin "2") (pinfunction "2_2") (pintype "passive"))
      (node (ref "C2") (pin "2") (pinfunction "2_2") (pintype "passive"))
      (node (ref "C2_BAT") (pin "2") (pinfunction "2_2") (pintype "passive"))
      (node (ref "C3") (pin "-") (pinfunction "-_-") (pintype "passive"))
      (node (ref "C4_USB") (pin "2") (pinfunction "2_2") (pintype "passive"))
      (node (ref "C5") (pin "2") (pinfunction "2_2") (pintype "passive"))
      (node (ref "C5_USB") (pin "2") (pinfunction "2_2") (pintype "passive"))
      (node (ref "C6") (pin "2") (pinfunction "2_2") (pintype "passive"))
      (node (ref "C7") (pin "2") (pinfunction "2_2") (pintype "passive"))
      (node (ref "C8") (pin "2") (pinfunction "2_2") (pintype "passive"))
      (node (ref "C9") (pin "2") (pinfunction "2_2") (pintype "passive"))
      (node (ref "CHANGE_BUTTON") (pin "1") (pinfunction "1_1") (pintype "passive"))
      (node (ref "CHANGE_BUTTON") (pin "2") (pinfunction "2_2") (pintype "passive"))
      (node (ref "C_DELAY") (pin "2") (pinfunction "2_2") (pintype "passive"))
      (node (ref "D1") (pin "2") (pinfunction "GND_2") (pintype "bidirectional"))
      (node (ref "D10") (pin "1") (pinfunction "1_1") (pintype "passive"))
      (node (ref "D11") (pin "1") (pinfunction "1_1") (pintype "passive"))
      (node (ref "D12") (pin "1") (pinfunction "1_1") (pintype "passive"))
      (node (ref "D3") (pin "1") (pinfunction "K_1") (pintype "bidirectional"))
      (node (ref "D6") (pin "1") (pinfunction "1_1") (pintype "passive"))
      (node (ref "D8") (pin "1") (pinfunction "1_1") (pintype "passive"))
      (node (ref "D9") (pin "1") (pinfunction "1_1") (pintype "passive"))
      (node (ref "EPD_C1") (pin "2") (pinfunction "2_2") (pintype "passive"))
      (node (ref "EPD_C10") (pin "2") (pinfunction "2_2") (pintype "passive"))
      (node (ref "EPD_C11") (pin "2") (pinfunction "2_2") (pintype "passive"))
      (node (ref "EPD_C12") (pin "2") (pinfunction "2_2") (pintype "passive"))
      (node (ref "EPD_C2") (pin "2") (pinfunction "2_2") (pintype "passive"))
      (node (ref "EPD_C5") (pin "2") (pinfunction "2_2") (pintype "passive"))
      (node (ref "EPD_C6") (pin "2") (pinfunction "2_2") (pintype "passive"))
      (node (ref "EPD_C7") (pin "2") (pinfunction "2_2") (pintype "passive"))
      (node (ref "EPD_C8") (pin "2") (pinfunction "2_2") (pintype "passive"))
      (node (ref "EPD_C9") (pin "2") (pinfunction "2_2") (pintype "passive"))
      (node (ref "IC1") (pin "3") (pinfunction "GND_3") (pintype "bidirectional"))
      (node (ref "IC4") (pin "2") (pinfunction "VSS_2") (pintype "bidirectional"))
      (node (ref "J1") (pin "17") (pinfunction "17_17") (pintype "bidirectional"))
      (node (ref "J1") (pin "8") (pinfunction "8_8") (pintype "bidirectional"))
      (node (ref "J1") (pin "MP1") (pinfunction "MP1_MP1") (pintype "bidirectional"))
      (node (ref "J1") (pin "MP2") (pinfunction "MP2_MP2") (pintype "bidirectional"))
      (node (ref "J2") (pin "A1") (pinfunction "A1_A1") (pintype "bidirectional"))
      (node (ref "J2") (pin "A12") (pinfunction "A12_A12") (pintype "bidirectional"))
      (node (ref "J2") (pin "B1") (pinfunction "B1_B1") (pintype "bidirectional"))
      (node (ref "J2") (pin "B12") (pinfunction "B12_B12") (pintype "bidirectional"))
      (node (ref "J2") (pin "MP1") (pinfunction "MP1_MP1") (pintype "bidirectional"))
      (node (ref "J2") (pin "MP2") (pinfunction "MP2_MP2") (pintype "bidirectional"))
      (node (ref "J2") (pin "MP3") (pinfunction "MP3_MP3") (pintype "bidirectional"))
      (node (ref "J2") (pin "MP4") (pinfunction "MP4_MP4") (pintype "bidirectional"))
      (node (ref "J3") (pin "1") (pinfunction "1_1") (pintype "power_in"))
      (node (ref "J4") (pin "G1") (pinfunction "GND_1_G1") (pintype "bidirectional"))
      (node (ref "J4") (pin "G2") (pinfunction "GND_2_G2") (pintype "bidirectional"))
      (node (ref "J4") (pin "G3") (pinfunction "GND_3_G3") (pintype "bidirectional"))
      (node (ref "J4") (pin "G4") (pinfunction "GND_4_G4") (pintype "bidirectional"))
      (node (ref "J4") (pin "P6") (pinfunction "VSS_P6") (pintype "bidirectional"))
      (node (ref "R1_PWRBUS") (pin "1") (pinfunction "1_1") (pintype "passive"))
      (node (ref "R2") (pin "1") (pinfunction "1_1") (pintype "passive"))
      (node (ref "R2-USB") (pin "2") (pinfunction "2_2") (pintype "passive"))
      (node (ref "R2-USB1") (pin "1") (pinfunction "1_1") (pintype "passive"))
      (node (ref "R2_BAT") (pin "1") (pinfunction "1_1") (pintype "passive"))
      (node (ref "R4") (pin "2") (pinfunction "2_2") (pintype "passive"))
      (node (ref "RESET_BUTTON") (pin "1") (pinfunction "1_1") (pintype "passive"))
      (node (ref "RESET_BUTTON") (pin "2") (pinfunction "2_2") (pintype "passive"))
      (node (ref "SENSOR2") (pin "1") (pinfunction "GND_1") (pintype "power_in"))
      (node (ref "SENSOR2") (pin "5") (pinfunction "SDO_5") (pintype "bidirectional"))
      (node (ref "SENSOR2") (pin "7") (pinfunction "GND_7") (pintype "power_in"))
      (node (ref "SJ1") (pin "1") (pinfunction "1_1") (pintype "passive"))
      (node (ref "TP4") (pin "TP") (pinfunction "TP_TP") (pintype "input"))
      (node (ref "TP5") (pin "TP") (pinfunction "TP_TP") (pintype "input"))
      (node (ref "U1") (pin "4") (pinfunction "GND_4") (pintype "power_in"))
      (node (ref "U1") (pin "9") (pinfunction "EXP_9") (pintype "passive"))
      (node (ref "U2") (pin "1") (pinfunction "GND_1") (pintype "power_in"))
      (node (ref "U2") (pin "28") (pinfunction "GND_28") (pintype "power_in"))
      (node (ref "U2") (pin "29_1") (pinfunction "GND_29_1") (pintype "power_in"))
      (node (ref "U2") (pin "29_2") (pinfunction "GND_29_2") (pintype "power_in"))
      (node (ref "U2") (pin "29_3") (pinfunction "GND_29_3") (pintype "power_in"))
      (node (ref "U2") (pin "29_4") (pinfunction "GND_29_4") (pintype "power_in"))
      (node (ref "U2") (pin "29_5") (pinfunction "GND_29_5") (pintype "power_in"))
      (node (ref "U2") (pin "29_6") (pinfunction "GND_29_6") (pintype "power_in"))
      (node (ref "U2") (pin "29_7") (pinfunction "GND_29_7") (pintype "power_in"))
      (node (ref "U2") (pin "29_8") (pinfunction "GND_29_8") (pintype "power_in"))
      (node (ref "U2") (pin "29_9") (pinfunction "GND_29_9") (pintype "power_in"))
      (node (ref "U3") (pin "13") (pinfunction "GND_13") (pintype "power_in"))
      (node (ref "U4") (pin "1") (pinfunction "CTG_1") (pintype "power_in"))
      (node (ref "U4") (pin "4") (pinfunction "GND_4") (pintype "power_in"))
      (node (ref "U4") (pin "6") (pinfunction "QSTRT_6") (pintype "input"))
      (node (ref "U4") (pin "9") (pinfunction "EP_9") (pintype "power_in"))
      (node (ref "U5") (pin "2") (pinfunction "VSS_2") (pintype "power_in"))
    )
    (net (code "14") (name "GPIO8") (class "Default")
      (node (ref "R1") (pin "2") (pinfunction "2_2") (pintype "passive"))
      (node (ref "U2") (pin "10") (pinfunction "IO8_10") (pintype "bidirectional"))
    )
    (net (code "15") (name "I2C_PW") (class "Default")
      (node (ref "C1") (pin "1") (pinfunction "1_1") (pintype "passive"))
      (node (ref "C2") (pin "1") (pinfunction "1_1") (pintype "passive"))
      (node (ref "R1_PINH") (pin "2") (pinfunction "2_2") (pintype "passive"))
      (node (ref "R2_PINH") (pin "2") (pinfunction "2_2") (pintype "passive"))
      (node (ref "SENSOR2") (pin "2") (pinfunction "CSB_2") (pintype "input"))
      (node (ref "SENSOR2") (pin "6") (pinfunction "VDDIO_6") (pintype "power_in"))
      (node (ref "SENSOR2") (pin "8") (pinfunction "VDD_8") (pintype "power_in"))
      (node (ref "U2") (pin "17") (pinfunction "IO19_17") (pintype "bidirectional"))
    )
    (net (code "16") (name "INT_RTC") (class "Default")
      (node (ref "R1_PINH1") (pin "1") (pinfunction "1_1") (pintype "passive"))
      (node (ref "TP15") (pin "TP") (pinfunction "TP_TP") (pintype "input"))
      (node (ref "U2") (pin "8") (pinfunction "IO0_8") (pintype "bidirectional"))
      (node (ref "U3") (pin "3") (pinfunction "SQW/~{INT}_3") (pintype "output"))
    )
    (net (code "17") (name "IO{slash}BOOT") (class "Default")
      (node (ref "BOOT_BUTTON") (pin "3") (pinfunction "3_3") (pintype "passive"))
      (node (ref "BOOT_BUTTON") (pin "4") (pinfunction "4_4") (pintype "passive"))
      (node (ref "C6") (pin "1") (pinfunction "1_1") (pintype "passive"))
      (node (ref "R_BOOT") (pin "2") (pinfunction "2_2") (pintype "passive"))
      (node (ref "U2") (pin "15") (pinfunction "IO9_15") (pintype "bidirectional"))
    )
    (net (code "18") (name "IO{slash}CHANGE") (class "Default")
      (node (ref "C10") (pin "1") (pinfunction "1_1") (pintype "passive"))
      (node (ref "CHANGE_BUTTON") (pin "3") (pinfunction "3_3") (pintype "passive"))
      (node (ref "CHANGE_BUTTON") (pin "4") (pinfunction "4_4") (pintype "passive"))
      (node (ref "R_CHANGE") (pin "2") (pinfunction "2_2") (pintype "passive"))
      (node (ref "U2") (pin "23") (pinfunction "IO15_23") (pintype "bidirectional"))
    )
    (net (code "19") (name "MISO") (class "Default")
      (node (ref "D12") (pin "2") (pinfunction "2_2") (pintype "passive"))
      (node (ref "J4") (pin "P7") (pinfunction "DAT0_P7") (pintype "bidirectional"))
      (node (ref "R8") (pin "1") (pinfunction "1_1") (pintype "passive"))
      (node (ref "TP6") (pin "TP") (pinfunction "TP_TP") (pintype "input"))
      (node (ref "U1") (pin "2") (pinfunction "DO(IO1)_2") (pintype "bidirectional"))
      (node (ref "U2") (pin "27") (pinfunction "IO2_27") (pintype "bidirectional"))
    )
    (net (code "20") (name "MOSI") (class "Default")
      (node (ref "D11") (pin "2") (pinfunction "2_2") (pintype "passive"))
      (node (ref "J1") (pin "14") (pinfunction "14_14") (pintype "bidirectional"))
      (node (ref "J4") (pin "P3") (pinfunction "CMD_P3") (pintype "bidirectional"))
      (node (ref "R7") (pin "1") (pinfunction "1_1") (pintype "passive"))
      (node (ref "TP7") (pin "TP") (pinfunction "TP_TP") (pintype "input"))
      (node (ref "U1") (pin "5") (pinfunction "DI(IO0)_5") (pintype "bidirectional"))
      (node (ref "U2") (pin "7") (pinfunction "IO7_7") (pintype "bidirectional"))
    )
    (net (code "21") (name "Net-(CHG_LED-PadC)") (class "Default")
      (node (ref "CHG_LED") (pin "C") (pinfunction "C_C") (pintype "passive"))
      (node (ref "R1_BAT") (pin "2") (pinfunction "2_2") (pintype "passive"))
    )
    (net (code "22") (name "Net-(D2-CATHODE)") (class "Default")
      (node (ref "C1_BAT1") (pin "1") (pinfunction "1_1") (pintype "passive"))
      (node (ref "D2") (pin "2") (pinfunction "CATHODE_2") (pintype "bidirectional"))
      (node (ref "IC4") (pin "1") (pinfunction "VIN_1") (pintype "bidirectional"))
      (node (ref "IC4") (pin "3") (pinfunction "CE_3") (pintype "bidirectional"))
      (node (ref "Q1") (pin "2") (pinfunction "S_2") (pintype "bidirectional"))
    )
    (net (code "23") (name "Net-(D3-A)") (class "Default")
      (node (ref "C4") (pin "1") (pinfunction "1_1") (pintype "passive"))
      (node (ref "D3") (pin "2") (pinfunction "A_2") (pintype "bidirectional"))
      (node (ref "D4") (pin "1") (pinfunction "K_1") (pintype "bidirectional"))
    )
    (net (code "24") (name "Net-(D7-CATHODE)") (class "Default")
      (node (ref "D7") (pin "2") (pinfunction "CATHODE_2") (pintype "bidirectional"))
      (node (ref "R_CAPACITOR") (pin "2") (pinfunction "2_2") (pintype "passive"))
    )
    (net (code "25") (name "Net-(EPD_C1-Pad1)") (class "Default")
      (node (ref "EPD_C1") (pin "1") (pinfunction "1_1") (pintype "passive"))
      (node (ref "J1") (pin "4") (pinfunction "4_4") (pintype "bidirectional"))
    )
    (net (code "26") (name "Net-(EPD_C2-Pad1)") (class "Default")
      (node (ref "EPD_C2") (pin "1") (pinfunction "1_1") (pintype "passive"))
      (node (ref "J1") (pin "5") (pinfunction "5_5") (pintype "bidirectional"))
    )
    (net (code "27") (name "Net-(EPD_C6-Pad1)") (class "Default")
      (node (ref "EPD_C6") (pin "1") (pinfunction "1_1") (pintype "passive"))
      (node (ref "J1") (pin "18") (pinfunction "18_18") (pintype "bidirectional"))
    )
    (net (code "28") (name "Net-(EPD_C7-Pad1)") (class "Default")
      (node (ref "EPD_C7") (pin "1") (pinfunction "1_1") (pintype "passive"))
      (node (ref "J1") (pin "19") (pinfunction "19_19") (pintype "bidirectional"))
    )
    (net (code "29") (name "Net-(EPD_C8-Pad1)") (class "Default")
      (node (ref "EPD_C8") (pin "1") (pinfunction "1_1") (pintype "passive"))
      (node (ref "J1") (pin "20") (pinfunction "20_20") (pintype "bidirectional"))
    )
    (net (code "30") (name "Net-(EPD_C10-Pad1)") (class "Default")
      (node (ref "EPD_C10") (pin "1") (pinfunction "1_1") (pintype "passive"))
      (node (ref "J1") (pin "22") (pinfunction "22_22") (pintype "bidirectional"))
    )
    (net (code "31") (name "Net-(EPD_C12-Pad1)") (class "Default")
      (node (ref "EPD_C12") (pin "1") (pinfunction "1_1") (pintype "passive"))
      (node (ref "J1") (pin "24") (pinfunction "24_24") (pintype "bidirectional"))
    )
    (net (code "32") (name "Net-(IC1-CT)") (class "Default")
      (node (ref "C_DELAY") (pin "1") (pinfunction "1_1") (pintype "passive"))
      (node (ref "IC1") (pin "5") (pinfunction "CT_5") (pintype "bidirectional"))
    )
    (net (code "33") (name "Net-(J2-PadA5)") (class "Default")
      (node (ref "J2") (pin "A5") (pinfunction "A5_A5") (pintype "bidirectional"))
      (node (ref "R2-USB1") (pin "2") (pinfunction "2_2") (pintype "passive"))
    )
    (net (code "34") (name "Net-(J2-PadB5)") (class "Default")
      (node (ref "J2") (pin "B5") (pinfunction "B5_B5") (pintype "bidirectional"))
      (node (ref "R2-USB") (pin "1") (pinfunction "1_1") (pintype "passive"))
    )
    (net (code "35") (name "Net-(U5-PROG)") (class "Default")
      (node (ref "R2_BAT") (pin "2") (pinfunction "2_2") (pintype "passive"))
      (node (ref "U5") (pin "5") (pinfunction "PROG_5") (pintype "input"))
    )
    (net (code "36") (name "Net-(U5-STAT)") (class "Default")
      (node (ref "R1_BAT") (pin "1") (pinfunction "1_1") (pintype "passive"))
      (node (ref "U5") (pin "1") (pinfunction "STAT_1") (pintype "output"))
    )
    (net (code "37") (name "PREVGH") (class "Default")
      (node (ref "D5") (pin "1") (pinfunction "K_1") (pintype "bidirectional"))
      (node (ref "EPD_C9") (pin "1") (pinfunction "1_1") (pintype "passive"))
      (node (ref "J1") (pin "21") (pinfunction "21_21") (pintype "bidirectional"))
    )
    (net (code "38") (name "PREVGL") (class "Default")
      (node (ref "D4") (pin "2") (pinfunction "A_2") (pintype "bidirectional"))
      (node (ref "EPD_C11") (pin "1") (pinfunction "1_1") (pintype "passive"))
      (node (ref "J1") (pin "23") (pinfunction "23_23") (pintype "bidirectional"))
    )
    (net (code "39") (name "RESE") (class "Default")
      (node (ref "J1") (pin "3") (pinfunction "3_3") (pintype "bidirectional"))
      (node (ref "Q3") (pin "2") (pinfunction "S_2") (pintype "bidirectional"))
      (node (ref "R3") (pin "1") (pinfunction "1_1") (pintype "passive"))
    )
    (net (code "40") (name "RESE'") (class "Default")
      (node (ref "R2") (pin "2") (pinfunction "2_2") (pintype "passive"))
      (node (ref "R3") (pin "2") (pinfunction "2_2") (pintype "passive"))
      (node (ref "SJ1") (pin "2") (pinfunction "2_2") (pintype "passive"))
    )
    (net (code "41") (name "RESET") (class "Default")
      (node (ref "C5") (pin "1") (pinfunction "1_1") (pintype "passive"))
      (node (ref "IC1") (pin "1") (pinfunction "VOUT_1") (pintype "bidirectional"))
      (node (ref "RESET_BUTTON") (pin "3") (pinfunction "3_3") (pintype "passive"))
      (node (ref "RESET_BUTTON") (pin "4") (pinfunction "4_4") (pintype "passive"))
      (node (ref "R_RESET") (pin "2") (pinfunction "2_2") (pintype "passive"))
      (node (ref "U2") (pin "3") (pinfunction "EN_3") (pintype "input"))
    )
    (net (code "42") (name "RTC_RST") (class "Default")
      (node (ref "U2") (pin "16") (pinfunction "IO18_16") (pintype "bidirectional"))
      (node (ref "U3") (pin "4") (pinfunction "~{RST}_4") (pintype "input"))
    )
    (net (code "43") (name "RX") (class "Default")
      (node (ref "TP2") (pin "TP") (pinfunction "TP_TP") (pintype "input"))
      (node (ref "U2") (pin "24") (pinfunction "RXD0/GPIO17_24") (pintype "bidirectional"))
    )
    (net (code "44") (name "SCK") (class "Default")
      (node (ref "D10") (pin "2") (pinfunction "2_2") (pintype "passive"))
      (node (ref "J1") (pin "13") (pinfunction "13_13") (pintype "bidirectional"))
      (node (ref "J4") (pin "P5") (pinfunction "CLK_P5") (pintype "bidirectional"))
      (node (ref "R6") (pin "1") (pinfunction "1_1") (pintype "passive"))
      (node (ref "TP8") (pin "TP") (pinfunction "TP_TP") (pintype "input"))
      (node (ref "U1") (pin "6") (pinfunction "CLK_6") (pintype "input"))
      (node (ref "U2") (pin "6") (pinfunction "IO6_6") (pintype "bidirectional"))
    )
    (net (code "45") (name "SCL") (class "Default")
      (node (ref "J3") (pin "4") (pinfunction "4_4") (pintype "passive"))
      (node (ref "R2_PINH") (pin "1") (pinfunction "1_1") (pintype "passive"))
      (node (ref "SENSOR2") (pin "4") (pinfunction "SCK_4") (pintype "input"))
      (node (ref "U2") (pin "20") (pinfunction "IO22_20") (pintype "bidirectional"))
      (node (ref "U3") (pin "16") (pinfunction "SCL_16") (pintype "input"))
      (node (ref "U4") (pin "7") (pinfunction "SCL_7") (pintype "input"))
    )
    (net (code "46") (name "SDA") (class "Default")
      (node (ref "J3") (pin "3") (pinfunction "3_3") (pintype "passive"))
      (node (ref "R1_PINH") (pin "1") (pinfunction "1_1") (pintype "passive"))
      (node (ref "SENSOR2") (pin "3") (pinfunction "SDI_3") (pintype "bidirectional"))
      (node (ref "U2") (pin "19") (pinfunction "IO21_19") (pintype "bidirectional"))
      (node (ref "U3") (pin "15") (pinfunction "SDA_15") (pintype "bidirectional"))
      (node (ref "U4") (pin "8") (pinfunction "SDA_8") (pintype "bidirectional"))
    )
    (net (code "47") (name "SRC") (class "Default")
      (node (ref "C4") (pin "2") (pinfunction "2_2") (pintype "passive"))
      (node (ref "D5") (pin "2") (pinfunction "A_2") (pintype "bidirectional"))
      (node (ref "L1") (pin "1") (pinfunction "1_1") (pintype "passive"))
      (node (ref "Q3") (pin "3") (pinfunction "D_3") (pintype "bidirectional"))
    )
    (net (code "48") (name "SS_SD") (class "Default")
      (node (ref "D8") (pin "2") (pinfunction "2_2") (pintype "passive"))
      (node (ref "J4") (pin "P2") (pinfunction "CD/DAT3_P2") (pintype "bidirectional"))
      (node (ref "R10") (pin "1") (pinfunction "1_1") (pintype "passive"))
      (node (ref "U2") (pin "4") (pinfunction "IO4_4") (pintype "bidirectional"))
    )
    (net (code "49") (name "TX") (class "Default")
      (node (ref "TP1") (pin "TP") (pinfunction "TP_TP") (pintype "input"))
      (node (ref "U2") (pin "25") (pinfunction "TXD0/GPIO16_25") (pintype "bidirectional"))
    )
    (net (code "50") (name "USB_D+") (class "Default")
      (node (ref "D1") (pin "1") (pinfunction "I/O1_1_1") (pintype "bidirectional"))
      (node (ref "U2") (pin "14") (pinfunction "IO13_14") (pintype "bidirectional"))
    )
    (net (code "51") (name "USB_D-") (class "Default")
      (node (ref "D1") (pin "3") (pinfunction "I/O2_1_3") (pintype "bidirectional"))
      (node (ref "U2") (pin "13") (pinfunction "IO12_13") (pintype "bidirectional"))
    )
    (net (code "52") (name "VBAT") (class "Default")
      (node (ref "C2_BAT") (pin "1") (pinfunction "1_1") (pintype "passive"))
      (node (ref "Q1") (pin "3") (pinfunction "D_3") (pintype "bidirectional"))
      (node (ref "TP3") (pin "TP") (pinfunction "TP_TP") (pintype "input"))
      (node (ref "U4") (pin "2") (pinfunction "CELL_2") (pintype "power_in"))
      (node (ref "U4") (pin "3") (pinfunction "VDD_3") (pintype "power_in"))
      (node (ref "U5") (pin "3") (pinfunction "VBAT_3") (pintype "power_in"))
    )
    (net (code "53") (name "VBUS") (class "Default")
      (node (ref "C1_BAT") (pin "1") (pinfunction "1_1") (pintype "passive"))
      (node (ref "C4_USB") (pin "1") (pinfunction "1_1") (pintype "passive"))
      (node (ref "C5_USB") (pin "1") (pinfunction "1_1") (pintype "passive"))
      (node (ref "CHG_LED") (pin "A") (pinfunction "A_A") (pintype "passive"))
      (node (ref "D1") (pin "5") (pinfunction "VBUS_5") (pintype "bidirectional"))
      (node (ref "D2") (pin "1") (pinfunction "ANODE_1") (pintype "bidirectional"))
      (node (ref "PFMF.050.1") (pin "2") (pinfunction "2_2") (pintype "passive"))
      (node (ref "Q1") (pin "1") (pinfunction "G_1") (pintype "bidirectional"))
      (node (ref "R1_PWRBUS") (pin "2") (pinfunction "2_2") (pintype "passive"))
      (node (ref "TP14") (pin "TP") (pinfunction "TP_TP") (pintype "input"))
      (node (ref "U5") (pin "4") (pinfunction "VIN_4") (pintype "power_in"))
    )
    (net (code "54") (name "VRTC") (class "Default")
      (node (ref "C10_SUPERCAP") (pin "1") (pinfunction "1_1") (pintype "passive"))
      (node (ref "C8") (pin "1") (pinfunction "1_1") (pintype "passive"))
      (node (ref "R_CAPACITOR") (pin "1") (pinfunction "1_1") (pintype "passive"))
      (node (ref "U3") (pin "14") (pinfunction "VBAT_14") (pintype "power_in"))
    )
    (net (code "55") (name "VUSB") (class "Default")
      (node (ref "J2") (pin "A4") (pinfunction "A4_A4") (pintype "bidirectional"))
      (node (ref "J2") (pin "A9") (pinfunction "A9_A9") (pintype "bidirectional"))
      (node (ref "J2") (pin "B4") (pinfunction "B4_B4") (pintype "bidirectional"))
      (node (ref "J2") (pin "B9") (pinfunction "B9_B9") (pintype "bidirectional"))
      (node (ref "PFMF.050.1") (pin "1") (pinfunction "1_1") (pintype "passive"))
    )
    (net (code "56") (name "unconnected-(IC1-NC-Pad4)") (class "Default")
      (node (ref "IC1") (pin "4") (pinfunction "NC_4") (pintype "no_connect"))
    )
    (net (code "57") (name "unconnected-(IC4-NC-Pad4)") (class "Default")
      (node (ref "IC4") (pin "4") (pinfunction "NC_4") (pintype "no_connect"))
    )
    (net (code "58") (name "unconnected-(J1-Pad1)") (class "Default")
      (node (ref "J1") (pin "1") (pinfunction "1_1") (pintype "bidirectional"))
    )
    (net (code "59") (name "unconnected-(J1-Pad6)") (class "Default")
      (node (ref "J1") (pin "6") (pinfunction "6_6") (pintype "bidirectional"))
    )
    (net (code "60") (name "unconnected-(J1-Pad7)") (class "Default")
      (node (ref "J1") (pin "7") (pinfunction "7_7") (pintype "bidirectional"))
    )
    (net (code "61") (name "unconnected-(J2-PadA8)") (class "Default")
      (node (ref "J2") (pin "A8") (pinfunction "A8_A8") (pintype "bidirectional"))
    )
    (net (code "62") (name "unconnected-(J2-PadB8)") (class "Default")
      (node (ref "J2") (pin "B8") (pinfunction "B8_B8") (pintype "bidirectional"))
    )
    (net (code "63") (name "unconnected-(J4-DAT1-PadP8)") (class "Default")
      (node (ref "J4") (pin "P8") (pinfunction "DAT1_P8") (pintype "bidirectional"))
    )
    (net (code "64") (name "unconnected-(J4-DAT2-PadP1)") (class "Default")
      (node (ref "J4") (pin "P1") (pinfunction "DAT2_P1") (pintype "bidirectional"))
    )
    (net (code "65") (name "unconnected-(J4-DETECTION_1-PadS1)") (class "Default")
      (node (ref "J4") (pin "S1") (pinfunction "DETECTION_1_S1") (pintype "bidirectional"))
    )
    (net (code "66") (name "unconnected-(J4-DETECTION_2-PadS2)") (class "Default")
      (node (ref "J4") (pin "S2") (pinfunction "DETECTION_2_S2") (pintype "bidirectional"))
    )
    (net (code "67") (name "unconnected-(U2-NC-Pad22)") (class "Default")
      (node (ref "U2") (pin "22") (pinfunction "NC_22") (pintype "no_connect"))
    )
    (net (code "68") (name "unconnected-(U4-~{ALERT}-Pad5)") (class "Default")
      (node (ref "U4") (pin "5") (pinfunction "~{ALERT}_5") (pintype "output"))
    )
  )
)
